# untitled.net
KiCad netlist of a schematic drawn in EAGLE
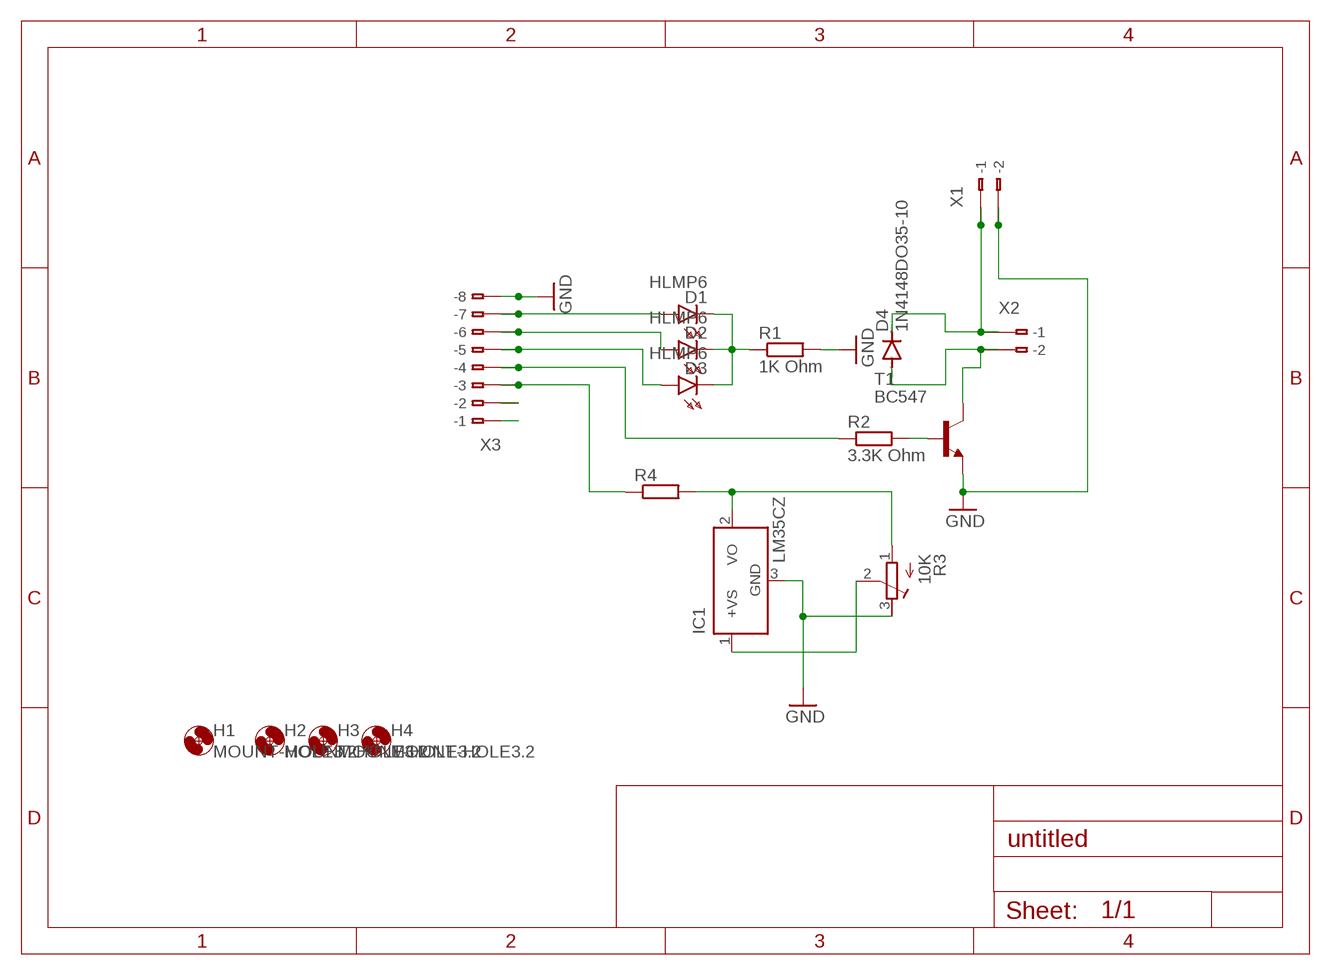
[diagram p0: schematic, sheet 1]

(export (version "E")
  (design (tool "Eeschema 10.0.6"))
  (components
    (comp (ref "D1")
      (value "HLMP6")
      (footprint "eagle-import:HLMP6")
      (fields (field (name "MF") "AGILENT TECHNOLOGIES") (field (name "MPN") "HLMP-6500"))
      (libsource (lib "eagle-import") (part "HLMP6"))
    )
    (comp (ref "D2")
      (value "HLMP6")
      (footprint "eagle-import:HLMP6")
      (fields (field (name "MF") "AGILENT TECHNOLOGIES") (field (name "MPN") "HLMP-6500"))
      (libsource (lib "eagle-import") (part "HLMP6"))
    )
    (comp (ref "D3")
      (value "HLMP6")
      (footprint "eagle-import:HLMP6")
      (fields (field (name "MF") "AGILENT TECHNOLOGIES") (field (name "MPN") "HLMP-6500"))
      (libsource (lib "eagle-import") (part "HLMP6"))
    )
    (comp (ref "D4")
      (value "1N4148DO35-10")
      (footprint "eagle-import:DO35-10")
      (libsource (lib "eagle-import") (part "1N4148DO35-10"))
    )
    (comp (ref "H1")
      (value "MOUNT-HOLE3.2")
      (footprint "eagle-import:3,2")
      (libsource (lib "eagle-import") (part "MOUNT-HOLE3.2"))
    )
    (comp (ref "H2")
      (value "MOUNT-HOLE3.2")
      (footprint "eagle-import:3,2")
      (libsource (lib "eagle-import") (part "MOUNT-HOLE3.2"))
    )
    (comp (ref "H3")
      (value "MOUNT-HOLE3.2")
      (footprint "eagle-import:3,2")
      (libsource (lib "eagle-import") (part "MOUNT-HOLE3.2"))
    )
    (comp (ref "H4")
      (value "MOUNT-HOLE3.2")
      (footprint "eagle-import:3,2")
      (libsource (lib "eagle-import") (part "MOUNT-HOLE3.2"))
    )
    (comp (ref "IC1")
      (value "LM35CZ")
      (footprint "eagle-import:TO92")
      (libsource (lib "eagle-import") (part "LM35CZ"))
    )
    (comp (ref "R1")
      (value "1K Ohm")
      (footprint "eagle-import:0411_15")
      (libsource (lib "eagle-import") (part "R-EU_0411/15"))
    )
    (comp (ref "R2")
      (value "3.3K Ohm")
      (footprint "eagle-import:0411_15")
      (libsource (lib "eagle-import") (part "R-EU_0411/15"))
    )
    (comp (ref "R3")
      (value "10K")
      (footprint "eagle-import:RTRIM3296X")
      (libsource (lib "eagle-import") (part "R-TRIMM3296X"))
    )
    (comp (ref "R4")
      (value "R-EU_0411/15")
      (footprint "eagle-import:0411_15")
      (libsource (lib "eagle-import") (part "R-EU_0411/15"))
    )
    (comp (ref "T1")
      (value "BC547")
      (footprint "eagle-import:TO92")
      (libsource (lib "eagle-import") (part "BC547"))
    )
    (comp (ref "X1")
      (value "233-102")
      (footprint "eagle-import:233-102")
      (libsource (lib "eagle-import") (part "233-102"))
    )
    (comp (ref "X2")
      (value "233-102")
      (footprint "eagle-import:233-102")
      (libsource (lib "eagle-import") (part "233-102"))
    )
    (comp (ref "X3")
      (value "233-108")
      (footprint "eagle-import:233-108")
      (libsource (lib "eagle-import") (part "233-108"))
    )
  )
  (nets
    (net (code "1") (name "GND") (class "Default")
      (node (ref "IC1") (pin "3") (pinfunction "GND_3") (pintype "power_in"))
      (node (ref "R1") (pin "2") (pinfunction "2_2") (pintype "passive"))
      (node (ref "R3") (pin "3") (pinfunction "E_3") (pintype "passive"))
      (node (ref "T1") (pin "1") (pinfunction "E_1") (pintype "passive"))
      (node (ref "X1") (pin "A2") (pinfunction "-2_A2") (pintype "passive"))
      (node (ref "X1") (pin "B2") (pinfunction "B-2_B2") (pintype "passive"))
      (node (ref "X3") (pin "A8") (pinfunction "-8_A8") (pintype "passive"))
      (node (ref "X3") (pin "B8") (pinfunction "B-8_B8") (pintype "passive"))
    )
    (net (code "2") (name "Net-(D1-PadK)") (class "Default")
      (node (ref "D1") (pin "K") (pinfunction "K_K") (pintype "passive"))
      (node (ref "D2") (pin "K") (pinfunction "K_K") (pintype "passive"))
      (node (ref "D3") (pin "K") (pinfunction "K_K") (pintype "passive"))
      (node (ref "R1") (pin "1") (pinfunction "1_1") (pintype "passive"))
    )
    (net (code "3") (name "Net-(IC1-+VS)") (class "Default")
      (node (ref "IC1") (pin "1") (pinfunction "+VS_1") (pintype "input"))
      (node (ref "R3") (pin "2") (pinfunction "S_2") (pintype "passive"))
    )
    (net (code "4") (name "Net-(IC1-VO)") (class "Default")
      (node (ref "IC1") (pin "2") (pinfunction "VO_2") (pintype "input"))
      (node (ref "R3") (pin "1") (pinfunction "A_1") (pintype "passive"))
      (node (ref "R4") (pin "2") (pinfunction "2_2") (pintype "passive"))
    )
    (net (code "5") (name "Net-(T1-B)") (class "Default")
      (node (ref "R2") (pin "2") (pinfunction "2_2") (pintype "passive"))
      (node (ref "T1") (pin "2") (pinfunction "B_2") (pintype "passive"))
    )
    (net (code "6") (name "Net-(T1-C)") (class "Default")
      (node (ref "D4") (pin "A") (pinfunction "A_A") (pintype "passive"))
      (node (ref "T1") (pin "3") (pinfunction "C_3") (pintype "passive"))
      (node (ref "X2") (pin "A2") (pinfunction "-2_A2") (pintype "passive"))
      (node (ref "X2") (pin "B2") (pinfunction "B-2_B2") (pintype "passive"))
    )
    (net (code "7") (name "Net-(X1--1)") (class "Default")
      (node (ref "D4") (pin "C") (pinfunction "C_C") (pintype "passive"))
      (node (ref "X1") (pin "A1") (pinfunction "-1_A1") (pintype "passive"))
      (node (ref "X1") (pin "B1") (pinfunction "B-1_B1") (pintype "passive"))
      (node (ref "X2") (pin "A1") (pinfunction "-1_A1") (pintype "passive"))
      (node (ref "X2") (pin "B1") (pinfunction "B-1_B1") (pintype "passive"))
    )
    (net (code "8") (name "Net-(X3--1)") (class "Default")
      (node (ref "X3") (pin "A1") (pinfunction "-1_A1") (pintype "passive"))
      (node (ref "X3") (pin "B1") (pinfunction "B-1_B1") (pintype "passive"))
    )
    (net (code "9") (name "Net-(X3--2)") (class "Default")
      (node (ref "X3") (pin "A2") (pinfunction "-2_A2") (pintype "passive"))
      (node (ref "X3") (pin "B2") (pinfunction "B-2_B2") (pintype "passive"))
    )
    (net (code "10") (name "Net-(X3--3)") (class "Default")
      (node (ref "R4") (pin "1") (pinfunction "1_1") (pintype "passive"))
      (node (ref "X3") (pin "A3") (pinfunction "-3_A3") (pintype "passive"))
      (node (ref "X3") (pin "B3") (pinfunction "B-3_B3") (pintype "passive"))
    )
    (net (code "11") (name "Net-(X3--4)") (class "Default")
      (node (ref "R2") (pin "1") (pinfunction "1_1") (pintype "passive"))
      (node (ref "X3") (pin "A4") (pinfunction "-4_A4") (pintype "passive"))
      (node (ref "X3") (pin "B4") (pinfunction "B-4_B4") (pintype "passive"))
    )
    (net (code "12") (name "Net-(X3--5)") (class "Default")
      (node (ref "D3") (pin "A") (pinfunction "A_A") (pintype "passive"))
      (node (ref "X3") (pin "A5") (pinfunction "-5_A5") (pintype "passive"))
      (node (ref "X3") (pin "B5") (pinfunction "B-5_B5") (pintype "passive"))
    )
    (net (code "13") (name "Net-(X3--6)") (class "Default")
      (node (ref "D2") (pin "A") (pinfunction "A_A") (pintype "passive"))
      (node (ref "X3") (pin "A6") (pinfunction "-6_A6") (pintype "passive"))
      (node (ref "X3") (pin "B6") (pinfunction "B-6_B6") (pintype "passive"))
    )
    (net (code "14") (name "Net-(X3--7)") (class "Default")
      (node (ref "D1") (pin "A") (pinfunction "A_A") (pintype "passive"))
      (node (ref "X3") (pin "A7") (pinfunction "-7_A7") (pintype "passive"))
      (node (ref "X3") (pin "B7") (pinfunction "B-7_B7") (pintype "passive"))
    )
  )
)
